# 01-POWER.net
KiCad netlist of a schematic drawn in Altium Designer
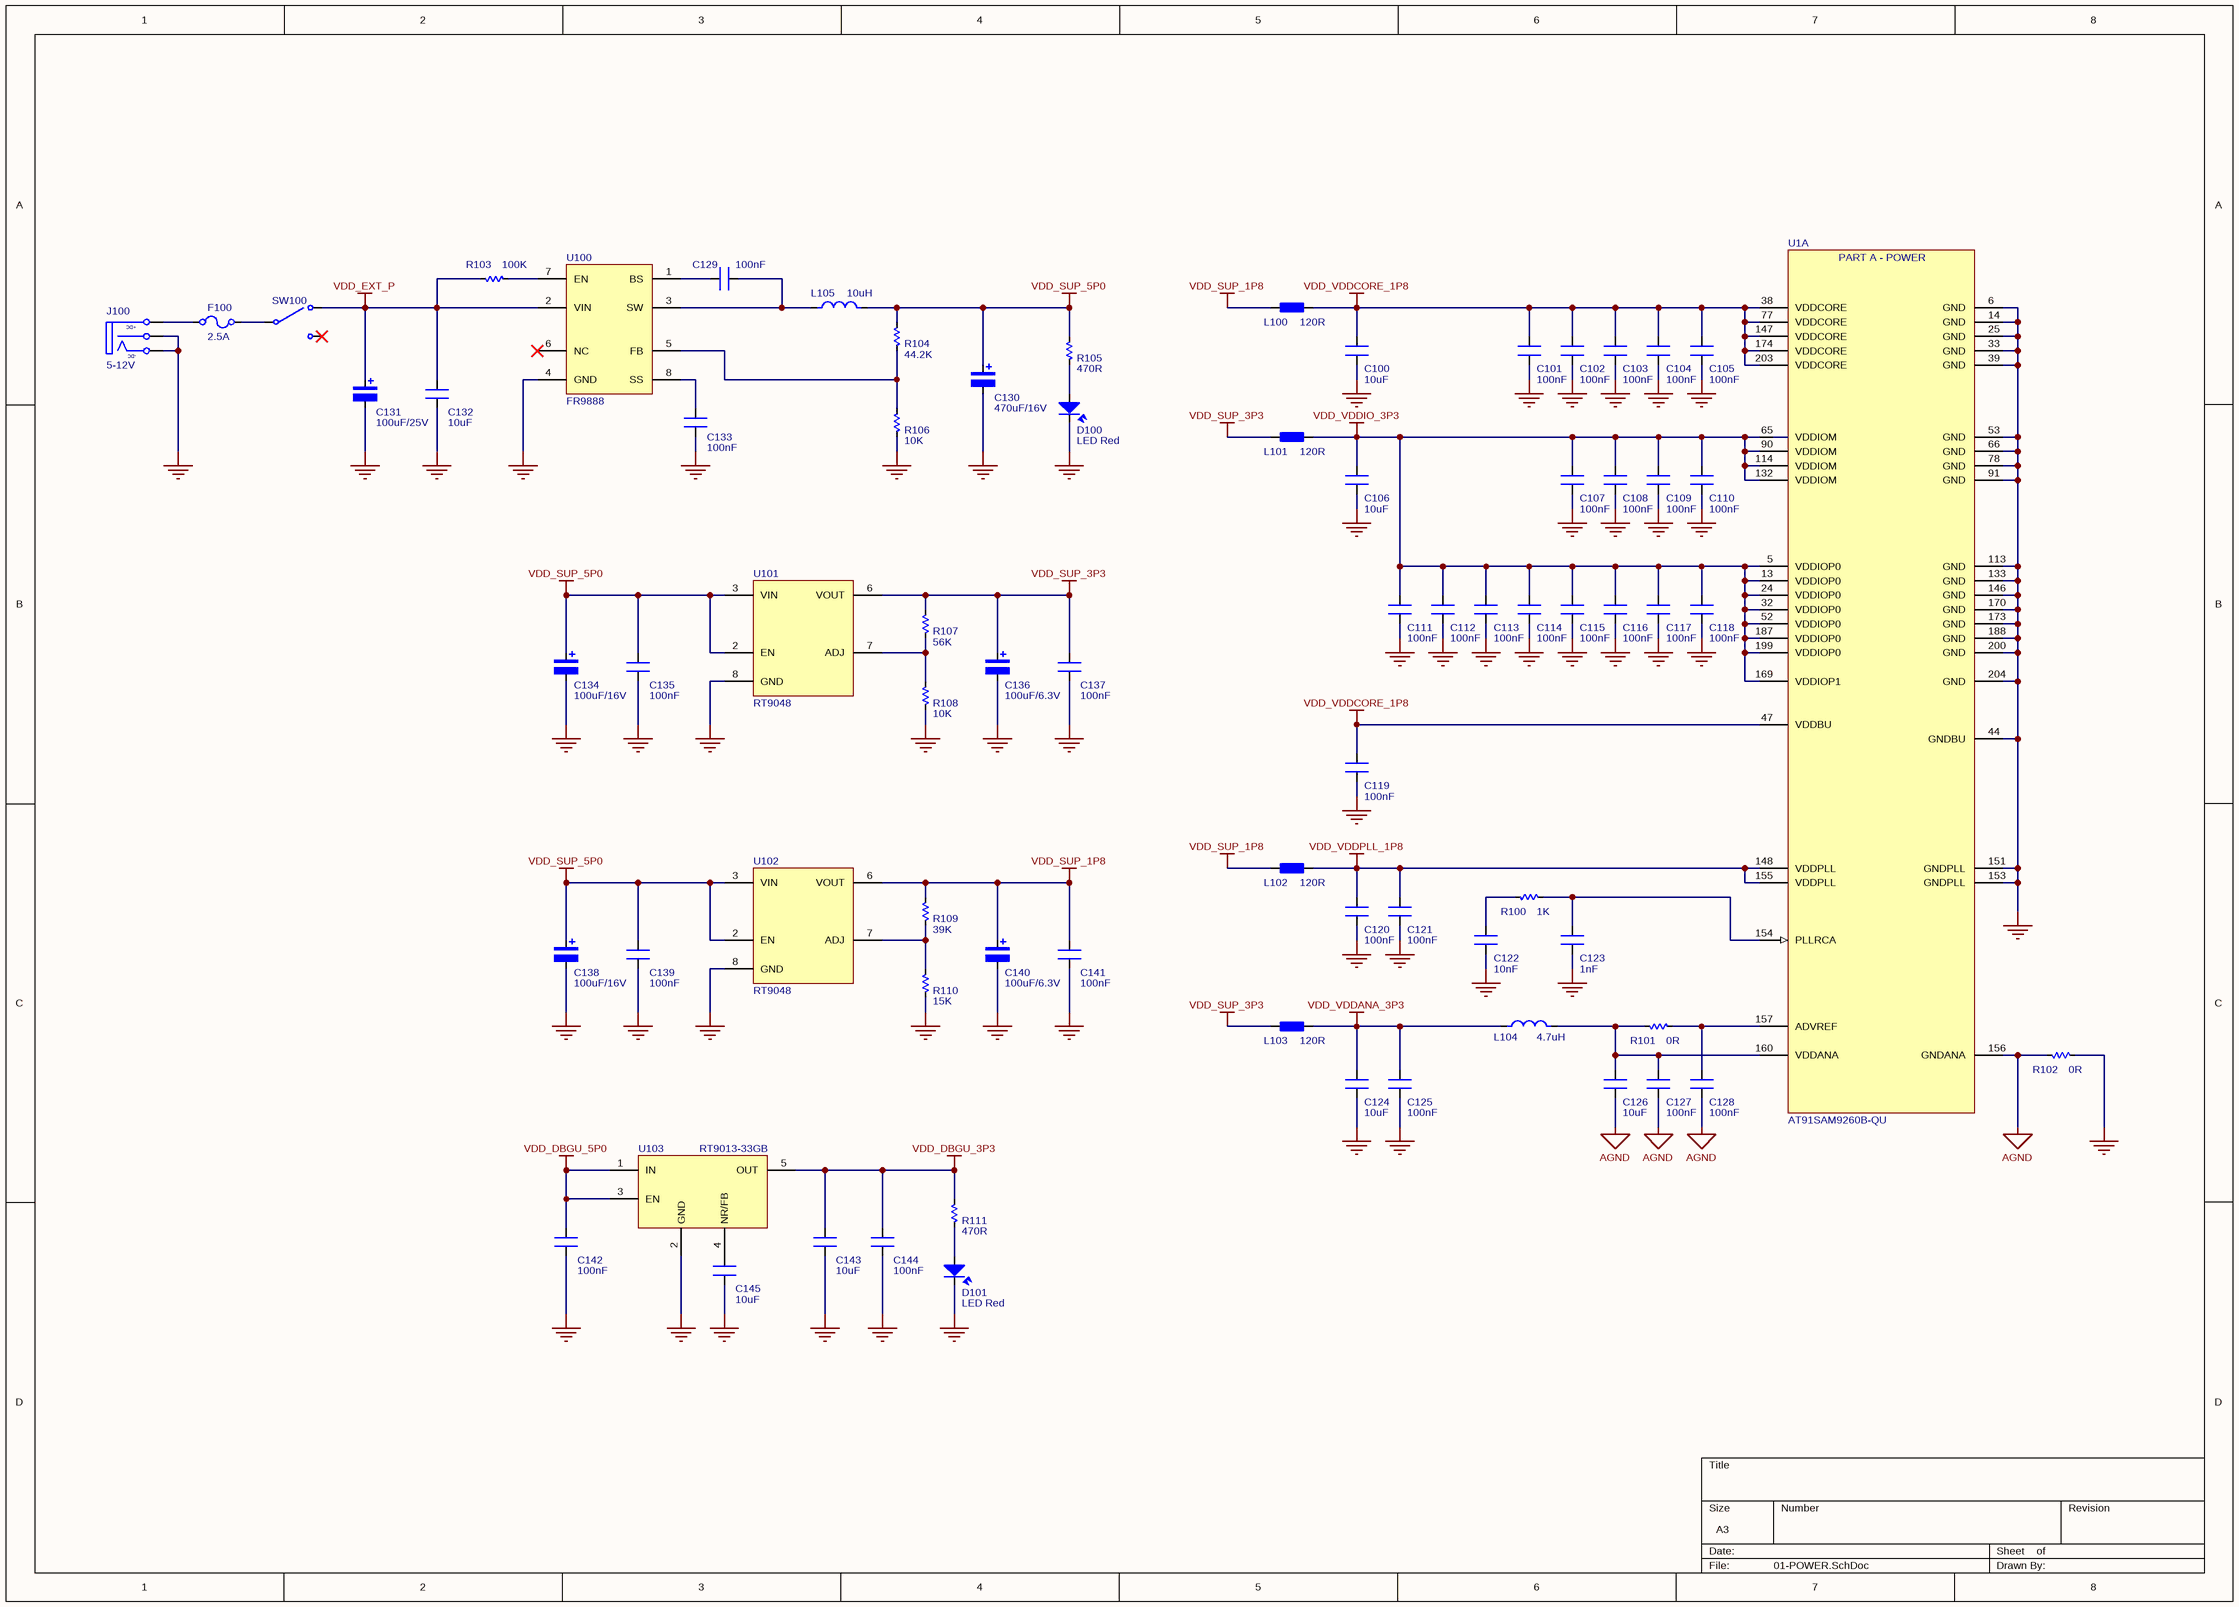
[diagram p0: 01-POWER.SchDoc]

(export (version "E")
  (design (tool "Eeschema 10.0.6"))
  (components
    (comp (ref "C100")
      (value "10uF")
      (footprint "CN-SMD-0603")
      (description "Ceramic Capacitor SMD 0603 10uF ±20% 10V")
      (fields (field (name "Comment") "Capacitor"))
      (libsource (lib "AS50") (part "Cap"))
    )
    (comp (ref "C101")
      (value "100nF")
      (footprint "CN-SMD-0603")
      (description "Ceramic Capacitor SMD 0603 100nF ±20% 10V")
      (fields (field (name "Comment") "Capacitor"))
      (libsource (lib "AS50") (part "Cap"))
    )
    (comp (ref "C102")
      (value "100nF")
      (footprint "CN-SMD-0603")
      (description "Ceramic Capacitor SMD 0603 100nF ±20% 10V")
      (fields (field (name "Comment") "Capacitor"))
      (libsource (lib "AS50") (part "Cap"))
    )
    (comp (ref "C103")
      (value "100nF")
      (footprint "CN-SMD-0603")
      (description "Ceramic Capacitor SMD 0603 100nF ±20% 10V")
      (fields (field (name "Comment") "Capacitor"))
      (libsource (lib "AS50") (part "Cap"))
    )
    (comp (ref "C104")
      (value "100nF")
      (footprint "CN-SMD-0603")
      (description "Ceramic Capacitor SMD 0603 100nF ±20% 10V")
      (fields (field (name "Comment") "Capacitor"))
      (libsource (lib "AS50") (part "Cap"))
    )
    (comp (ref "C105")
      (value "100nF")
      (footprint "CN-SMD-0603")
      (description "Ceramic Capacitor SMD 0603 100nF ±20% 10V")
      (fields (field (name "Comment") "Capacitor"))
      (libsource (lib "AS50") (part "Cap"))
    )
    (comp (ref "C106")
      (value "10uF")
      (footprint "CN-SMD-0603")
      (description "Ceramic Capacitor SMD 0603 10uF ±20% 10V")
      (fields (field (name "Comment") "Capacitor"))
      (libsource (lib "AS50") (part "Cap"))
    )
    (comp (ref "C107")
      (value "100nF")
      (footprint "CN-SMD-0603")
      (description "Ceramic Capacitor SMD 0603 100nF ±20% 10V")
      (fields (field (name "Comment") "Capacitor"))
      (libsource (lib "AS50") (part "Cap"))
    )
    (comp (ref "C108")
      (value "100nF")
      (footprint "CN-SMD-0603")
      (description "Ceramic Capacitor SMD 0603 100nF ±20% 10V")
      (fields (field (name "Comment") "Capacitor"))
      (libsource (lib "AS50") (part "Cap"))
    )
    (comp (ref "C109")
      (value "100nF")
      (footprint "CN-SMD-0603")
      (description "Ceramic Capacitor SMD 0603 100nF ±20% 10V")
      (fields (field (name "Comment") "Capacitor"))
      (libsource (lib "AS50") (part "Cap"))
    )
    (comp (ref "C110")
      (value "100nF")
      (footprint "CN-SMD-0603")
      (description "Ceramic Capacitor SMD 0603 100nF ±20% 10V")
      (fields (field (name "Comment") "Capacitor"))
      (libsource (lib "AS50") (part "Cap"))
    )
    (comp (ref "C111")
      (value "100nF")
      (footprint "CN-SMD-0603")
      (description "Ceramic Capacitor SMD 0603 100nF ±20% 10V")
      (fields (field (name "Comment") "Capacitor"))
      (libsource (lib "AS50") (part "Cap"))
    )
    (comp (ref "C112")
      (value "100nF")
      (footprint "CN-SMD-0603")
      (description "Ceramic Capacitor SMD 0603 100nF ±20% 10V")
      (fields (field (name "Comment") "Capacitor"))
      (libsource (lib "AS50") (part "Cap"))
    )
    (comp (ref "C113")
      (value "100nF")
      (footprint "CN-SMD-0603")
      (description "Ceramic Capacitor SMD 0603 100nF ±20% 10V")
      (fields (field (name "Comment") "Capacitor"))
      (libsource (lib "AS50") (part "Cap"))
    )
    (comp (ref "C114")
      (value "100nF")
      (footprint "CN-SMD-0603")
      (description "Ceramic Capacitor SMD 0603 100nF ±20% 10V")
      (fields (field (name "Comment") "Capacitor"))
      (libsource (lib "AS50") (part "Cap"))
    )
    (comp (ref "C115")
      (value "100nF")
      (footprint "CN-SMD-0603")
      (description "Ceramic Capacitor SMD 0603 100nF ±20% 10V")
      (fields (field (name "Comment") "Capacitor"))
      (libsource (lib "AS50") (part "Cap"))
    )
    (comp (ref "C116")
      (value "100nF")
      (footprint "CN-SMD-0603")
      (description "Ceramic Capacitor SMD 0603 100nF ±20% 10V")
      (fields (field (name "Comment") "Capacitor"))
      (libsource (lib "AS50") (part "Cap"))
    )
    (comp (ref "C117")
      (value "100nF")
      (footprint "CN-SMD-0603")
      (description "Ceramic Capacitor SMD 0603 100nF ±20% 10V")
      (fields (field (name "Comment") "Capacitor"))
      (libsource (lib "AS50") (part "Cap"))
    )
    (comp (ref "C118")
      (value "100nF")
      (footprint "CN-SMD-0603")
      (description "Ceramic Capacitor SMD 0603 100nF ±20% 10V")
      (fields (field (name "Comment") "Capacitor"))
      (libsource (lib "AS50") (part "Cap"))
    )
    (comp (ref "C119")
      (value "100nF")
      (footprint "CN-SMD-0603")
      (description "Ceramic Capacitor SMD 0603 100nF ±20% 10V")
      (fields (field (name "Comment") "Capacitor"))
      (libsource (lib "AS50") (part "Cap"))
    )
    (comp (ref "C120")
      (value "100nF")
      (footprint "CN-SMD-0603")
      (description "Ceramic Capacitor SMD 0603 100nF ±20% 10V")
      (fields (field (name "Comment") "Capacitor"))
      (libsource (lib "AS50") (part "Cap"))
    )
    (comp (ref "C121")
      (value "100nF")
      (footprint "CN-SMD-0603")
      (description "Ceramic Capacitor SMD 0603 100nF ±20% 10V")
      (fields (field (name "Comment") "Capacitor"))
      (libsource (lib "AS50") (part "Cap"))
    )
    (comp (ref "C122")
      (value "10nF")
      (footprint "CN-SMD-0603")
      (description "Ceramic Capacitor SMD 0603 10nF ±20% 10V")
      (fields (field (name "Comment") "Capacitor"))
      (libsource (lib "AS50") (part "Cap"))
    )
    (comp (ref "C123")
      (value "1nF")
      (footprint "CN-SMD-0603")
      (description "Ceramic Capacitor SMD 0603 1nF ±20% 10V")
      (fields (field (name "Comment") "Capacitor"))
      (libsource (lib "AS50") (part "Cap"))
    )
    (comp (ref "C124")
      (value "10uF")
      (footprint "CN-SMD-0603")
      (description "Ceramic Capacitor SMD 0603 10uF ±20% 10V")
      (fields (field (name "Comment") "Capacitor"))
      (libsource (lib "AS50") (part "Cap"))
    )
    (comp (ref "C125")
      (value "100nF")
      (footprint "CN-SMD-0603")
      (description "Ceramic Capacitor SMD 0603 100nF ±20% 10V")
      (fields (field (name "Comment") "Capacitor"))
      (libsource (lib "AS50") (part "Cap"))
    )
    (comp (ref "C126")
      (value "10uF")
      (footprint "CN-SMD-0603")
      (description "Ceramic Capacitor SMD 0603 10uF ±20% 10V")
      (fields (field (name "Comment") "Capacitor"))
      (libsource (lib "AS50") (part "Cap"))
    )
    (comp (ref "C127")
      (value "100nF")
      (footprint "CN-SMD-0603")
      (description "Ceramic Capacitor SMD 0603 100nF ±20% 10V")
      (fields (field (name "Comment") "Capacitor"))
      (libsource (lib "AS50") (part "Cap"))
    )
    (comp (ref "C128")
      (value "100nF")
      (footprint "CN-SMD-0603")
      (description "Ceramic Capacitor SMD 0603 100nF ±20% 10V")
      (fields (field (name "Comment") "Capacitor"))
      (libsource (lib "AS50") (part "Cap"))
    )
    (comp (ref "C129")
      (value "100nF")
      (footprint "CN-SMD-0603")
      (description "Ceramic Capacitor SMD 0603 100nF ±20% 10V")
      (fields (field (name "Comment") "Capacitor"))
      (libsource (lib "AS50") (part "Cap"))
    )
    (comp (ref "C130")
      (value "470uF/16V")
      (footprint "C-ALU-SMD-D6.3W6.6L7.7")
      (description "Aluminum Capacitor SMD 470uF 16V")
      (fields (field (name "Comment") "Cap_Aluminum"))
      (libsource (lib "AS50") (part "Cap_Aluminum"))
    )
    (comp (ref "C131")
      (value "100uF/25V")
      (footprint "C-ALU-SMD-D6.3W6.6L7.7")
      (description "Aluminum Capacitor SMD 100uF 25V")
      (fields (field (name "Comment") "Cap_Aluminum"))
      (libsource (lib "AS50") (part "Cap_Aluminum"))
    )
    (comp (ref "C132")
      (value "10uF")
      (footprint "CN-SMD-0603")
      (description "Ceramic Capacitor SMD 0805 10uF ±20% 25V")
      (fields (field (name "Comment") "Capacitor"))
      (libsource (lib "AS50") (part "Cap"))
    )
    (comp (ref "C133")
      (value "100nF")
      (footprint "CN-SMD-0603")
      (description "Ceramic Capacitor SMD 0603 100nF ±20% 10V")
      (fields (field (name "Comment") "Capacitor"))
      (libsource (lib "AS50") (part "Cap"))
    )
    (comp (ref "C134")
      (value "100uF/16V")
      (footprint "C-TAL-SMD-7343-31")
      (description "Tantalum Capacitor SMD 7343 100uF ±20% 16V")
      (fields (field (name "Comment") "Cap_Tantalum"))
      (libsource (lib "AS50") (part "Cap_Tantalum"))
    )
    (comp (ref "C135")
      (value "100nF")
      (footprint "CN-SMD-0603")
      (description "Ceramic Capacitor SMD 0805 100nF ±20% 25V")
      (fields (field (name "Comment") "Capacitor"))
      (libsource (lib "AS50") (part "Cap"))
    )
    (comp (ref "C136")
      (value "100uF/6.3V")
      (footprint "C-TAL-SMD-3216-18")
      (description "Tantalum Capacitor SMD 3216 100uF ±20% 6.3V")
      (fields (field (name "Comment") "Cap_Tantalum"))
      (libsource (lib "AS50") (part "Cap_Tantalum"))
    )
    (comp (ref "C137")
      (value "100nF")
      (footprint "CN-SMD-0603")
      (description "Ceramic Capacitor SMD 0805 100nF ±20% 25V")
      (fields (field (name "Comment") "Capacitor"))
      (libsource (lib "AS50") (part "Cap"))
    )
    (comp (ref "C138")
      (value "100uF/16V")
      (footprint "C-TAL-SMD-7343-31")
      (description "Tantalum Capacitor SMD 7343 100uF ±20% 16V")
      (fields (field (name "Comment") "Cap_Tantalum"))
      (libsource (lib "AS50") (part "Cap_Tantalum"))
    )
    (comp (ref "C139")
      (value "100nF")
      (footprint "CN-SMD-0603")
      (description "Ceramic Capacitor SMD 0805 100nF ±20% 25V")
      (fields (field (name "Comment") "Capacitor"))
      (libsource (lib "AS50") (part "Cap"))
    )
    (comp (ref "C140")
      (value "100uF/6.3V")
      (footprint "C-TAL-SMD-3216-18")
      (description "Tantalum Capacitor SMD 3216 100uF ±20% 6.3V")
      (fields (field (name "Comment") "Cap_Tantalum"))
      (libsource (lib "AS50") (part "Cap_Tantalum"))
    )
    (comp (ref "C141")
      (value "100nF")
      (footprint "CN-SMD-0603")
      (description "Ceramic Capacitor SMD 0805 100nF ±20% 25V")
      (fields (field (name "Comment") "Capacitor"))
      (libsource (lib "AS50") (part "Cap"))
    )
    (comp (ref "C142")
      (value "100nF")
      (footprint "CN-SMD-0603")
      (description "Ceramic Capacitor SMD 0805 100nF ±20% 25V")
      (fields (field (name "Comment") "Capacitor"))
      (libsource (lib "AS50") (part "Cap"))
    )
    (comp (ref "C143")
      (value "10uF")
      (footprint "CN-SMD-0603")
      (description "Ceramic Capacitor SMD 0805 10uF ±20% 25V")
      (fields (field (name "Comment") "Capacitor"))
      (libsource (lib "AS50") (part "Cap"))
    )
    (comp (ref "C144")
      (value "100nF")
      (footprint "CN-SMD-0603")
      (description "Ceramic Capacitor SMD 0805 100nF ±20% 25V")
      (fields (field (name "Comment") "Capacitor"))
      (libsource (lib "AS50") (part "Cap"))
    )
    (comp (ref "C145")
      (value "10uF")
      (footprint "CN-SMD-0603")
      (description "Ceramic Capacitor SMD 0805 10uF ±20% 25V")
      (fields (field (name "Comment") "Capacitor"))
      (libsource (lib "AS50") (part "Cap"))
    )
    (comp (ref "D100")
      (value "LED Red")
      (footprint "LED-SMD-0805-RED")
      (description "Light Emitting Diode SMD 0805 red color")
      (libsource (lib "AS50") (part "LED"))
    )
    (comp (ref "D101")
      (value "LED Red")
      (footprint "LED-SMD-0805-RED")
      (description "Light Emitting Diode SMD 0805 red color")
      (libsource (lib "AS50") (part "LED"))
    )
    (comp (ref "F100")
      (value "2.5A")
      (footprint "FUSE-SMD-1812")
      (description "Fuse SMD1812 2.5A")
      (libsource (lib "AS50") (part "FUSE"))
    )
    (comp (ref "J100")
      (value "5-12V")
      (footprint "JACK-DC_5.5x2.1")
      (description "DC Power Jack input 5.5x2.1mm")
      (libsource (lib "AS50") (part "DC_INPUT"))
    )
    (comp (ref "L100")
      (value "120R")
      (footprint "L-SMD-0603")
      (description "Ferrite bead SMD 0603 120 Ohm @100MHz")
      (fields (field (name "Comment") "Ferrite bead"))
      (libsource (lib "AS50") (part "Ferrite bead"))
    )
    (comp (ref "L101")
      (value "120R")
      (footprint "L-SMD-0603")
      (description "Ferrite bead SMD 0603 120 Ohm @100MHz")
      (fields (field (name "Comment") "Ferrite bead"))
      (libsource (lib "AS50") (part "Ferrite bead"))
    )
    (comp (ref "L102")
      (value "120R")
      (footprint "L-SMD-0603")
      (description "Ferrite bead SMD 0603 120 Ohm @100MHz")
      (fields (field (name "Comment") "Ferrite bead"))
      (libsource (lib "AS50") (part "Ferrite bead"))
    )
    (comp (ref "L103")
      (value "120R")
      (footprint "L-SMD-0603")
      (description "Ferrite bead SMD 0603 120 Ohm @100MHz")
      (fields (field (name "Comment") "Ferrite bead"))
      (libsource (lib "AS50") (part "Ferrite bead"))
    )
    (comp (ref "L104")
      (value "4.7uH")
      (footprint "L-SMD-0603")
      (description "Common Inductor SMD 0603 4.7uH ±20%")
      (fields (field (name "Comment") "Inductor"))
      (libsource (lib "AS50") (part "Inductor"))
    )
    (comp (ref "L105")
      (value "10uH")
      (footprint "L-SMD-0630")
      (description "Power Inductor SMD 6.6x6.6x3mm")
      (fields (field (name "Comment") "Inductor"))
      (libsource (lib "") (part "Inductor_1"))
    )
    (comp (ref "R100")
      (value "1K")
      (footprint "RES-SMD-0603")
      (description "Resistor SMD 0603 1K 1% 0.1W")
      (fields (field (name "Comment") "Resistor"))
      (libsource (lib "AS50") (part "Res"))
    )
    (comp (ref "R101")
      (value "0R")
      (footprint "RES-SMD-0603")
      (description "Resistor SMD 0603 0R 1% 0.1W")
      (fields (field (name "Comment") "Resistor"))
      (libsource (lib "AS50") (part "Res"))
    )
    (comp (ref "R102")
      (value "0R")
      (footprint "RES-SMD-0603")
      (description "Resistor SMD 0603 0R 1% 0.1W")
      (fields (field (name "Comment") "Resistor"))
      (libsource (lib "AS50") (part "Res"))
    )
    (comp (ref "R103")
      (value "100K")
      (footprint "RES-SMD-0603")
      (description "Resistor SMD 0603 100K 1% 0.1W")
      (fields (field (name "Comment") "Resistor"))
      (libsource (lib "AS50") (part "Res"))
    )
    (comp (ref "R104")
      (value "44.2K")
      (footprint "RES-SMD-0603")
      (description "Resistor SMD 0603 44.2K 1% 0.1W")
      (fields (field (name "Comment") "Resistor"))
      (libsource (lib "AS50") (part "Res"))
    )
    (comp (ref "R105")
      (value "470R")
      (footprint "RES-SMD-0603")
      (description "Resistor SMD 0603 470R 1% 0.1W")
      (fields (field (name "Comment") "Resistor"))
      (libsource (lib "AS50") (part "Res"))
    )
    (comp (ref "R106")
      (value "10K")
      (footprint "RES-SMD-0603")
      (description "Resistor SMD 0603 10K 1% 0.1W")
      (fields (field (name "Comment") "Resistor"))
      (libsource (lib "AS50") (part "Res"))
    )
    (comp (ref "R107")
      (value "56K")
      (footprint "RES-SMD-0603")
      (description "Resistor SMD 0603 56K 1% 0.1W")
      (fields (field (name "Comment") "Resistor"))
      (libsource (lib "AS50") (part "Res"))
    )
    (comp (ref "R108")
      (value "10K")
      (footprint "RES-SMD-0603")
      (description "Resistor SMD 0603 10K 1% 0.1W")
      (fields (field (name "Comment") "Resistor"))
      (libsource (lib "AS50") (part "Res"))
    )
    (comp (ref "R109")
      (value "39K")
      (footprint "RES-SMD-0603")
      (description "Resistor SMD 0603 39K 1% 0.1W")
      (fields (field (name "Comment") "Resistor"))
      (libsource (lib "AS50") (part "Res"))
    )
    (comp (ref "R110")
      (value "15K")
      (footprint "RES-SMD-0603")
      (description "Resistor SMD 0603 15K 1% 0.1W")
      (fields (field (name "Comment") "Resistor"))
      (libsource (lib "AS50") (part "Res"))
    )
    (comp (ref "R111")
      (value "470R")
      (footprint "RES-SMD-0603")
      (description "Resistor SMD 0603 470R 1% 0.1W")
      (fields (field (name "Comment") "Resistor"))
      (libsource (lib "AS50") (part "Res"))
    )
    (comp (ref "SW100")
      (value "SW3-SLIDE")
      (footprint "SW3_SS12F23")
      (description "Slide Switch 3-pin")
      (libsource (lib "AS50") (part "SW3-SLIDE"))
    )
    (comp (ref "U1")
      (value "AT91SAM9260B-QU")
      (footprint "PQFP50P3060X3060X410-208N")
      (description "AT91 Series 180 MHz 32 kB Flash 8 kB SRAM 32-Bit Microcontroller - PQFP-208")
      (fields (field (name "MF") "Microchip"))
      (libsource (lib "AS50") (part "AT91SAM9260B-QU"))
    )
    (comp (ref "U100")
      (value "FR9888")
      (footprint "SOIC127P600X175_HS-9N")
      (description "23V, 3A, 340KHz Synchronous Step-Down\r\nDC/DC Converter")
      (libsource (lib "AS50") (part "FR9888"))
    )
    (comp (ref "U101")
      (value "RT9048")
      (footprint "SOIC127P600X175_HS-9N")
      (description "Richtek 2A, Low Input Voltage, Ultra-Low Dropout Linear Regulator with Enable")
      (libsource (lib "AS50") (part "RT9048"))
    )
    (comp (ref "U102")
      (value "RT9048")
      (footprint "SOIC127P600X175_HS-9N")
      (description "Richtek 2A, Low Input Voltage, Ultra-Low Dropout Linear Regulator with Enable")
      (libsource (lib "AS50") (part "RT9048"))
    )
    (comp (ref "U103")
      (value "RT9013-33GB")
      (footprint "SOT95P245X110-5N")
      (description "Cap-Free, NMOS, 500-mA Low-Dropout Regulator with Reverse Current Protection")
      (libsource (lib "AS50") (part "TPS73633DBVR"))
    )
  )
  (nets
    (net (code "1") (name "AGND") (class "Default")
      (node (ref "C126") (pin "1") (pinfunction "1_1") (pintype "passive"))
      (node (ref "C127") (pin "1") (pinfunction "1_1") (pintype "passive"))
      (node (ref "C128") (pin "1") (pinfunction "1_1") (pintype "passive"))
      (node (ref "R102") (pin "2") (pinfunction "2_2") (pintype "passive"))
      (node (ref "U1") (pin "156") (pinfunction "GNDANA_156") (pintype "power_in"))
    )
    (net (code "2") (name "GND") (class "Default")
      (node (ref "C100") (pin "1") (pinfunction "1_1") (pintype "passive"))
      (node (ref "C101") (pin "1") (pinfunction "1_1") (pintype "passive"))
      (node (ref "C102") (pin "1") (pinfunction "1_1") (pintype "passive"))
      (node (ref "C103") (pin "1") (pinfunction "1_1") (pintype "passive"))
      (node (ref "C104") (pin "1") (pinfunction "1_1") (pintype "passive"))
      (node (ref "C105") (pin "1") (pinfunction "1_1") (pintype "passive"))
      (node (ref "C106") (pin "1") (pinfunction "1_1") (pintype "passive"))
      (node (ref "C107") (pin "1") (pinfunction "1_1") (pintype "passive"))
      (node (ref "C108") (pin "1") (pinfunction "1_1") (pintype "passive"))
      (node (ref "C109") (pin "1") (pinfunction "1_1") (pintype "passive"))
      (node (ref "C110") (pin "1") (pinfunction "1_1") (pintype "passive"))
      (node (ref "C111") (pin "1") (pinfunction "1_1") (pintype "passive"))
      (node (ref "C112") (pin "1") (pinfunction "1_1") (pintype "passive"))
      (node (ref "C113") (pin "1") (pinfunction "1_1") (pintype "passive"))
      (node (ref "C114") (pin "1") (pinfunction "1_1") (pintype "passive"))
      (node (ref "C115") (pin "1") (pinfunction "1_1") (pintype "passive"))
      (node (ref "C116") (pin "1") (pinfunction "1_1") (pintype "passive"))
      (node (ref "C117") (pin "1") (pinfunction "1_1") (pintype "passive"))
      (node (ref "C118") (pin "1") (pinfunction "1_1") (pintype "passive"))
      (node (ref "C119") (pin "1") (pinfunction "1_1") (pintype "passive"))
      (node (ref "C120") (pin "1") (pinfunction "1_1") (pintype "passive"))
      (node (ref "C121") (pin "1") (pinfunction "1_1") (pintype "passive"))
      (node (ref "C122") (pin "1") (pinfunction "1_1") (pintype "passive"))
      (node (ref "C123") (pin "1") (pinfunction "1_1") (pintype "passive"))
      (node (ref "C124") (pin "1") (pinfunction "1_1") (pintype "passive"))
      (node (ref "C125") (pin "1") (pinfunction "1_1") (pintype "passive"))
      (node (ref "C130") (pin "2") (pinfunction "2_2") (pintype "passive"))
      (node (ref "C131") (pin "2") (pinfunction "2_2") (pintype "passive"))
      (node (ref "C132") (pin "1") (pinfunction "1_1") (pintype "passive"))
      (node (ref "C133") (pin "1") (pinfunction "1_1") (pintype "passive"))
      (node (ref "C134") (pin "2") (pinfunction "2_2") (pintype "passive"))
      (node (ref "C135") (pin "1") (pinfunction "1_1") (pintype "passive"))
      (node (ref "C136") (pin "2") (pinfunction "2_2") (pintype "passive"))
      (node (ref "C137") (pin "1") (pinfunction "1_1") (pintype "passive"))
      (node (ref "C138") (pin "2") (pinfunction "2_2") (pintype "passive"))
      (node (ref "C139") (pin "1") (pinfunction "1_1") (pintype "passive"))
      (node (ref "C140") (pin "2") (pinfunction "2_2") (pintype "passive"))
      (node (ref "C141") (pin "1") (pinfunction "1_1") (pintype "passive"))
      (node (ref "C142") (pin "1") (pinfunction "1_1") (pintype "passive"))
      (node (ref "C143") (pin "1") (pinfunction "1_1") (pintype "passive"))
      (node (ref "C144") (pin "1") (pinfunction "1_1") (pintype "passive"))
      (node (ref "C145") (pin "1") (pinfunction "1_1") (pintype "passive"))
      (node (ref "D100") (pin "2") (pinfunction "2_2") (pintype "passive"))
      (node (ref "D101") (pin "2") (pinfunction "2_2") (pintype "passive"))
      (node (ref "J100") (pin "2") (pinfunction "-DC_2") (pintype "passive"))
      (node (ref "J100") (pin "3") (pintype "passive"))
      (node (ref "R102") (pin "1") (pinfunction "1_1") (pintype "passive"))
      (node (ref "R106") (pin "2") (pinfunction "2_2") (pintype "passive"))
      (node (ref "R108") (pin "2") (pinfunction "2_2") (pintype "passive"))
      (node (ref "R110") (pin "2") (pinfunction "2_2") (pintype "passive"))
      (node (ref "U1") (pin "113") (pinfunction "GND_113") (pintype "power_in"))
      (node (ref "U1") (pin "133") (pinfunction "GND_133") (pintype "power_in"))
      (node (ref "U1") (pin "14") (pinfunction "GND_14") (pintype "power_in"))
      (node (ref "U1") (pin "146") (pinfunction "GND_146") (pintype "power_in"))
      (node (ref "U1") (pin "151") (pinfunction "GNDPLL_151") (pintype "power_in"))
      (node (ref "U1") (pin "153") (pinfunction "GNDPLL_153") (pintype "power_in"))
      (node (ref "U1") (pin "170") (pinfunction "GND_170") (pintype "power_in"))
      (node (ref "U1") (pin "173") (pinfunction "GND_173") (pintype "power_in"))
      (node (ref "U1") (pin "188") (pinfunction "GND_188") (pintype "power_in"))
      (node (ref "U1") (pin "200") (pinfunction "GND_200") (pintype "power_in"))
      (node (ref "U1") (pin "204") (pinfunction "GND_204") (pintype "power_in"))
      (node (ref "U1") (pin "25") (pinfunction "GND_25") (pintype "power_in"))
      (node (ref "U1") (pin "33") (pinfunction "GND_33") (pintype "power_in"))
      (node (ref "U1") (pin "39") (pinfunction "GND_39") (pintype "power_in"))
      (node (ref "U1") (pin "44") (pinfunction "GNDBU_44") (pintype "power_in"))
      (node (ref "U1") (pin "53") (pinfunction "GND_53") (pintype "power_in"))
      (node (ref "U1") (pin "6") (pinfunction "GND_6") (pintype "power_in"))
      (node (ref "U1") (pin "66") (pinfunction "GND_66") (pintype "power_in"))
      (node (ref "U1") (pin "78") (pinfunction "GND_78") (pintype "power_in"))
      (node (ref "U1") (pin "91") (pinfunction "GND_91") (pintype "power_in"))
      (node (ref "U100") (pin "4") (pinfunction "GND_4") (pintype "passive"))
      (node (ref "U101") (pin "8") (pinfunction "GND_8") (pintype "power_in"))
      (node (ref "U102") (pin "8") (pinfunction "GND_8") (pintype "power_in"))
      (node (ref "U103") (pin "2") (pinfunction "GND_2") (pintype "power_in"))
    )
    (net (code "3") (name "Net-(C122-Pad2)") (class "Default")
      (node (ref "C122") (pin "2") (pinfunction "2_2") (pintype "passive"))
      (node (ref "R100") (pin "2") (pinfunction "2_2") (pintype "passive"))
    )
    (net (code "4") (name "Net-(D100-Pad1)") (class "Default")
      (node (ref "D100") (pin "1") (pinfunction "1_1") (pintype "passive"))
      (node (ref "R105") (pin "2") (pinfunction "2_2") (pintype "passive"))
    )
    (net (code "5") (name "Net-(D101-Pad1)") (class "Default")
      (node (ref "D101") (pin "1") (pinfunction "1_1") (pintype "passive"))
      (node (ref "R111") (pin "2") (pinfunction "2_2") (pintype "passive"))
    )
    (net (code "6") (name "Net-(F100-Pad2)") (class "Default")
      (node (ref "F100") (pin "2") (pintype "passive"))
      (node (ref "SW100") (pin "2") (pinfunction "2_2") (pintype "passive"))
    )
    (net (code "7") (name "Net-(J100-+DC)") (class "Default")
      (node (ref "F100") (pin "1") (pintype "passive"))
      (node (ref "J100") (pin "1") (pinfunction "+DC_1") (pintype "passive"))
    )
    (net (code "8") (name "Net-(U1A-ADVREF)") (class "Default")
      (node (ref "C128") (pin "2") (pinfunction "2_2") (pintype "passive"))
      (node (ref "R101") (pin "1") (pinfunction "1_1") (pintype "passive"))
      (node (ref "U1") (pin "157") (pinfunction "ADVREF_157") (pintype "power_in"))
    )
    (net (code "9") (name "Net-(U1A-PLLRCA)") (class "Default")
      (node (ref "C123") (pin "2") (pinfunction "2_2") (pintype "passive"))
      (node (ref "R100") (pin "1") (pinfunction "1_1") (pintype "passive"))
      (node (ref "U1") (pin "154") (pinfunction "PLLRCA_154") (pintype "input"))
    )
    (net (code "10") (name "Net-(U1A-VDDANA)") (class "Default")
      (node (ref "C126") (pin "2") (pinfunction "2_2") (pintype "passive"))
      (node (ref "C127") (pin "2") (pinfunction "2_2") (pintype "passive"))
      (node (ref "L104") (pin "1") (pinfunction "1_1") (pintype "passive"))
      (node (ref "R101") (pin "2") (pinfunction "2_2") (pintype "passive"))
      (node (ref "U1") (pin "160") (pinfunction "VDDANA_160") (pintype "power_in"))
    )
    (net (code "11") (name "Net-(U100-BS)") (class "Default")
      (node (ref "C129") (pin "2") (pinfunction "2_2") (pintype "passive"))
      (node (ref "U100") (pin "1") (pinfunction "BS_1") (pintype "passive"))
    )
    (net (code "12") (name "Net-(U100-EN)") (class "Default")
      (node (ref "R103") (pin "1") (pinfunction "1_1") (pintype "passive"))
      (node (ref "U100") (pin "7") (pinfunction "EN_7") (pintype "passive"))
    )
    (net (code "13") (name "Net-(U100-FB)") (class "Default")
      (node (ref "R104") (pin "2") (pinfunction "2_2") (pintype "passive"))
      (node (ref "R106") (pin "1") (pinfunction "1_1") (pintype "passive"))
      (node (ref "U100") (pin "5") (pinfunction "FB_5") (pintype "passive"))
    )
    (net (code "14") (name "Net-(U100-SS)") (class "Default")
      (node (ref "C133") (pin "2") (pinfunction "2_2") (pintype "passive"))
      (node (ref "U100") (pin "8") (pinfunction "SS_8") (pintype "passive"))
    )
    (net (code "15") (name "Net-(U100-SW)") (class "Default")
      (node (ref "C129") (pin "1") (pinfunction "1_1") (pintype "passive"))
      (node (ref "L105") (pin "1") (pinfunction "1_1") (pintype "passive"))
      (node (ref "U100") (pin "3") (pinfunction "SW_3") (pintype "passive"))
    )
    (net (code "16") (name "Net-(U101-ADJ)") (class "Default")
      (node (ref "R107") (pin "2") (pinfunction "2_2") (pintype "passive"))
      (node (ref "R108") (pin "1") (pinfunction "1_1") (pintype "passive"))
      (node (ref "U101") (pin "7") (pinfunction "ADJ_7") (pintype "power_in"))
    )
    (net (code "17") (name "Net-(U102-ADJ)") (class "Default")
      (node (ref "R109") (pin "2") (pinfunction "2_2") (pintype "passive"))
      (node (ref "R110") (pin "1") (pinfunction "1_1") (pintype "passive"))
      (node (ref "U102") (pin "7") (pinfunction "ADJ_7") (pintype "power_in"))
    )
    (net (code "18") (name "Net-(U103-NR{slash}FB)") (class "Default")
      (node (ref "C145") (pin "2") (pinfunction "2_2") (pintype "passive"))
      (node (ref "U103") (pin "4") (pinfunction "NR/FB_4") (pintype "power_in"))
    )
    (net (code "19") (name "VDD_DBGU_3P3") (class "Default")
      (node (ref "C143") (pin "2") (pinfunction "2_2") (pintype "passive"))
      (node (ref "C144") (pin "2") (pinfunction "2_2") (pintype "passive"))
      (node (ref "R111") (pin "1") (pinfunction "1_1") (pintype "passive"))
      (node (ref "U103") (pin "5") (pinfunction "OUT_5") (pintype "power_in"))
    )
    (net (code "20") (name "VDD_DBGU_5P0") (class "Default")
      (node (ref "C142") (pin "2") (pinfunction "2_2") (pintype "passive"))
      (node (ref "U103") (pin "1") (pinfunction "IN_1") (pintype "power_in"))
      (node (ref "U103") (pin "3") (pinfunction "EN_3") (pintype "power_in"))
    )
    (net (code "21") (name "VDD_EXT_P") (class "Default")
      (node (ref "C131") (pin "1") (pinfunction "1_1") (pintype "passive"))
      (node (ref "C132") (pin "2") (pinfunction "2_2") (pintype "passive"))
      (node (ref "R103") (pin "2") (pinfunction "2_2") (pintype "passive"))
      (node (ref "SW100") (pin "1") (pinfunction "1_1") (pintype "passive"))
      (node (ref "U100") (pin "2") (pinfunction "VIN_2") (pintype "passive"))
    )
    (net (code "22") (name "VDD_SUP_1P8") (class "Default")
      (node (ref "C140") (pin "1") (pinfunction "1_1") (pintype "passive"))
      (node (ref "C141") (pin "2") (pinfunction "2_2") (pintype "passive"))
      (node (ref "L100") (pin "2") (pinfunction "2_2") (pintype "passive"))
      (node (ref "L102") (pin "2") (pinfunction "2_2") (pintype "passive"))
      (node (ref "R109") (pin "1") (pinfunction "1_1") (pintype "passive"))
      (node (ref "U102") (pin "6") (pinfunction "VOUT_6") (pintype "power_in"))
    )
    (net (code "23") (name "VDD_SUP_3P3") (class "Default")
      (node (ref "C136") (pin "1") (pinfunction "1_1") (pintype "passive"))
      (node (ref "C137") (pin "2") (pinfunction "2_2") (pintype "passive"))
      (node (ref "L101") (pin "2") (pinfunction "2_2") (pintype "passive"))
      (node (ref "L103") (pin "2") (pinfunction "2_2") (pintype "passive"))
      (node (ref "R107") (pin "1") (pinfunction "1_1") (pintype "passive"))
      (node (ref "U101") (pin "6") (pinfunction "VOUT_6") (pintype "power_in"))
    )
    (net (code "24") (name "VDD_SUP_5P0") (class "Default")
      (node (ref "C130") (pin "1") (pinfunction "1_1") (pintype "passive"))
      (node (ref "C134") (pin "1") (pinfunction "1_1") (pintype "passive"))
      (node (ref "C135") (pin "2") (pinfunction "2_2") (pintype "passive"))
      (node (ref "C138") (pin "1") (pinfunction "1_1") (pintype "passive"))
      (node (ref "C139") (pin "2") (pinfunction "2_2") (pintype "passive"))
      (node (ref "L105") (pin "2") (pinfunction "2_2") (pintype "passive"))
      (node (ref "R104") (pin "1") (pinfunction "1_1") (pintype "passive"))
      (node (ref "R105") (pin "1") (pinfunction "1_1") (pintype "passive"))
      (node (ref "U101") (pin "2") (pinfunction "EN_2") (pintype "power_in"))
      (node (ref "U101") (pin "3") (pinfunction "VIN_3") (pintype "power_in"))
      (node (ref "U102") (pin "2") (pinfunction "EN_2") (pintype "power_in"))
      (node (ref "U102") (pin "3") (pinfunction "VIN_3") (pintype "power_in"))
    )
    (net (code "25") (name "VDD_VDDANA_3P3") (class "Default")
      (node (ref "C124") (pin "2") (pinfunction "2_2") (pintype "passive"))
      (node (ref "C125") (pin "2") (pinfunction "2_2") (pintype "passive"))
      (node (ref "L103") (pin "1") (pinfunction "1_1") (pintype "passive"))
      (node (ref "L104") (pin "2") (pinfunction "2_2") (pintype "passive"))
    )
    (net (code "26") (name "VDD_VDDCORE_1P8") (class "Default")
      (node (ref "C100") (pin "2") (pinfunction "2_2") (pintype "passive"))
      (node (ref "C101") (pin "2") (pinfunction "2_2") (pintype "passive"))
      (node (ref "C102") (pin "2") (pinfunction "2_2") (pintype "passive"))
      (node (ref "C103") (pin "2") (pinfunction "2_2") (pintype "passive"))
      (node (ref "C104") (pin "2") (pinfunction "2_2") (pintype "passive"))
      (node (ref "C105") (pin "2") (pinfunction "2_2") (pintype "passive"))
      (node (ref "C119") (pin "2") (pinfunction "2_2") (pintype "passive"))
      (node (ref "L100") (pin "1") (pinfunction "1_1") (pintype "passive"))
      (node (ref "U1") (pin "147") (pinfunction "VDDCORE_147") (pintype "power_in"))
      (node (ref "U1") (pin "174") (pinfunction "VDDCORE_174") (pintype "power_in"))
      (node (ref "U1") (pin "203") (pinfunction "VDDCORE_203") (pintype "power_in"))
      (node (ref "U1") (pin "38") (pinfunction "VDDCORE_38") (pintype "power_in"))
      (node (ref "U1") (pin "47") (pinfunction "VDDBU_47") (pintype "power_in"))
      (node (ref "U1") (pin "77") (pinfunction "VDDCORE_77") (pintype "power_in"))
    )
    (net (code "27") (name "VDD_VDDIO_3P3") (class "Default")
      (node (ref "C106") (pin "2") (pinfunction "2_2") (pintype "passive"))
      (node (ref "C107") (pin "2") (pinfunction "2_2") (pintype "passive"))
      (node (ref "C108") (pin "2") (pinfunction "2_2") (pintype "passive"))
      (node (ref "C109") (pin "2") (pinfunction "2_2") (pintype "passive"))
      (node (ref "C110") (pin "2") (pinfunction "2_2") (pintype "passive"))
      (node (ref "C111") (pin "2") (pinfunction "2_2") (pintype "passive"))
      (node (ref "C112") (pin "2") (pinfunction "2_2") (pintype "passive"))
      (node (ref "C113") (pin "2") (pinfunction "2_2") (pintype "passive"))
      (node (ref "C114") (pin "2") (pinfunction "2_2") (pintype "passive"))
      (node (ref "C115") (pin "2") (pinfunction "2_2") (pintype "passive"))
      (node (ref "C116") (pin "2") (pinfunction "2_2") (pintype "passive"))
      (node (ref "C117") (pin "2") (pinfunction "2_2") (pintype "passive"))
      (node (ref "C118") (pin "2") (pinfunction "2_2") (pintype "passive"))
      (node (ref "L101") (pin "1") (pinfunction "1_1") (pintype "passive"))
      (node (ref "U1") (pin "114") (pinfunction "VDDIOM_114") (pintype "power_in"))
      (node (ref "U1") (pin "13") (pinfunction "VDDIOP0_13") (pintype "power_in"))
      (node (ref "U1") (pin "132") (pinfunction "VDDIOM_132") (pintype "power_in"))
      (node (ref "U1") (pin "169") (pinfunction "VDDIOP1_169") (pintype "power_in"))
      (node (ref "U1") (pin "187") (pinfunction "VDDIOP0_187") (pintype "power_in"))
      (node (ref "U1") (pin "199") (pinfunction "VDDIOP0_199") (pintype "power_in"))
      (node (ref "U1") (pin "24") (pinfunction "VDDIOP0_24") (pintype "power_in"))
      (node (ref "U1") (pin "32") (pinfunction "VDDIOP0_32") (pintype "power_in"))
      (node (ref "U1") (pin "5") (pinfunction "VDDIOP0_5") (pintype "power_in"))
      (node (ref "U1") (pin "52") (pinfunction "VDDIOP0_52") (pintype "power_in"))
      (node (ref "U1") (pin "65") (pinfunction "VDDIOM_65") (pintype "power_in"))
      (node (ref "U1") (pin "90") (pinfunction "VDDIOM_90") (pintype "power_in"))
    )
    (net (code "28") (name "VDD_VDDPLL_1P8") (class "Default")
      (node (ref "C120") (pin "2") (pinfunction "2_2") (pintype "passive"))
      (node (ref "C121") (pin "2") (pinfunction "2_2") (pintype "passive"))
      (node (ref "L102") (pin "1") (pinfunction "1_1") (pintype "passive"))
      (node (ref "U1") (pin "148") (pinfunction "VDDPLL_148") (pintype "power_in"))
      (node (ref "U1") (pin "155") (pinfunction "VDDPLL_155") (pintype "power_in"))
    )
    (net (code "29") (name "unconnected-(SW100-Pad3)") (class "Default")
      (node (ref "SW100") (pin "3") (pinfunction "3_3") (pintype "passive+no_connect"))
    )
    (net (code "30") (name "unconnected-(U100-NC-Pad6)") (class "Default")
      (node (ref "U100") (pin "6") (pinfunction "NC_6") (pintype "passive+no_connect"))
    )
  )
)
